# bqZUM_PowerManager.net
KiCad netlist of a schematic drawn in Altium Designer
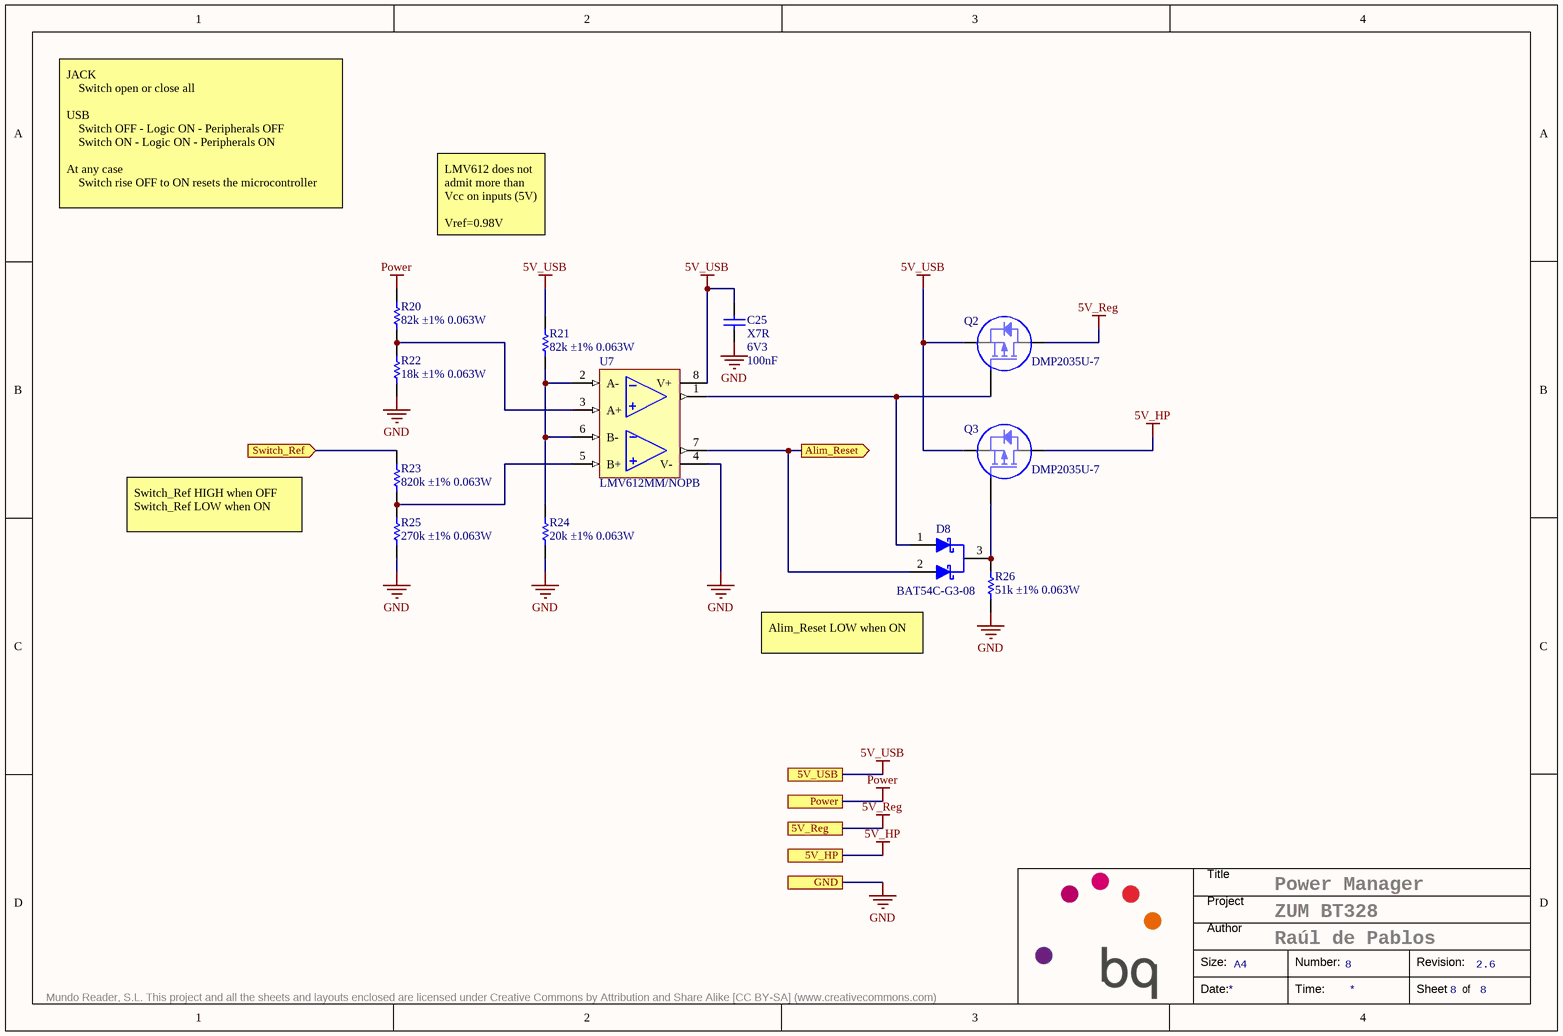
[diagram p0: bqZUM_PowerManager.SchDoc]

(export (version "E")
  (design (tool "Eeschema 10.0.6"))
  (components
    (comp (ref "C25")
      (value "Capacitor")
      (footprint "C0402")
      (fields
        (field (name "DIELECTRIC") "X7R")
        (field (name "VOLTAGE") "6V3")
        (field (name "CAPACITANCE") "100nF")
        (field (name "PART NUMBER") "C0402_100nF_6V3_±10%")
        (field (name "TOLERANCE") "±10%")
        (field (name "MANUFACTURER") "Kemet")
      )
      (libsource (lib "Pasives_Capacitor_SMD") (part "Capacitor"))
    )
    (comp (ref "D8")
      (value "BAT54C-G3-08")
      (footprint "SOT23-3")
      (description "Dual Schottky Diode Common Cathode")
      (fields (field (name "PART NUMBER") "BAT54C") (field (name "MANUFACTURER") "Vishay"))
      (libsource (lib "Semiconductors_Diodes") (part "Dual_Diode_Schottky_BAT54C"))
    )
    (comp (ref "Q2")
      (value "DMP2035U-7")
      (footprint "SOT23-3")
      (description "Mosfet Channel P Enhancement Mode")
      (fields (field (name "PART NUMBER") "DMP2035U") (field (name "MANUFACTURER") "Diodes Incorporated"))
      (libsource (lib "Semiconductors_Transistors") (part "Mosfet_P"))
    )
    (comp (ref "Q3")
      (value "DMP2035U-7")
      (footprint "SOT23-3")
      (description "Mosfet Channel P Enhancement Mode")
      (fields (field (name "PART NUMBER") "DMP2035U") (field (name "MANUFACTURER") "Diodes Incorporated"))
      (libsource (lib "Semiconductors_Transistors") (part "Mosfet_P"))
    )
    (comp (ref "R20")
      (value "82k ±1% 0.063W")
      (footprint "R0402")
      (description "Resistor")
      (fields (field (name "TOLERANCE") "±1%") (field (name "POWER") "0.063W"))
      (libsource (lib "Pasives_Resistor_SMD") (part "Resistor"))
    )
    (comp (ref "R21")
      (value "82k ±1% 0.063W")
      (footprint "R0402")
      (description "Resistor")
      (fields (field (name "TOLERANCE") "±1%") (field (name "POWER") "0.063W"))
      (libsource (lib "Pasives_Resistor_SMD") (part "Resistor"))
    )
    (comp (ref "R22")
      (value "18k ±1% 0.063W")
      (footprint "R0402")
      (description "Resistor")
      (fields (field (name "TOLERANCE") "±1%") (field (name "POWER") "0.063W"))
      (libsource (lib "Pasives_Resistor_SMD") (part "Resistor"))
    )
    (comp (ref "R23")
      (value "820k ±1% 0.063W")
      (footprint "R0402")
      (description "Resistor")
      (fields (field (name "TOLERANCE") "±1%") (field (name "POWER") "0.063W"))
      (libsource (lib "Pasives_Resistor_SMD") (part "Resistor"))
    )
    (comp (ref "R24")
      (value "20k ±1% 0.063W")
      (footprint "R0402")
      (description "Resistor")
      (fields (field (name "TOLERANCE") "±1%") (field (name "POWER") "0.063W"))
      (libsource (lib "Pasives_Resistor_SMD") (part "Resistor"))
    )
    (comp (ref "R25")
      (value "270k ±1% 0.063W")
      (footprint "R0402")
      (description "Resistor")
      (fields (field (name "TOLERANCE") "±1%") (field (name "POWER") "0.063W"))
      (libsource (lib "Pasives_Resistor_SMD") (part "Resistor"))
    )
    (comp (ref "R26")
      (value "51k ±1% 0.063W")
      (footprint "R0402")
      (description "Resistor")
      (fields (field (name "TOLERANCE") "±1%") (field (name "POWER") "0.063W"))
      (libsource (lib "Pasives_Resistor_SMD") (part "Resistor"))
    )
    (comp (ref "U7")
      (value "LMV612MM/NOPB")
      (footprint "VSSOP8")
      (description "Dual Operational Amplifier")
      (fields (field (name "PART NUMBER") "LMV612") (field (name "MANUFACTURER") "Texas Instruments"))
      (libsource (lib "Semiconductors_OA") (part "LMV612"))
    )
  )
  (nets
    (net (code "1") (name "/Alim_Reset") (class "Default")
      (node (ref "D8") (pin "2") (pinfunction "A2_2") (pintype "passive"))
      (node (ref "U7") (pin "7") (pinfunction "Out2_7") (pintype "output"))
    )
    (net (code "2") (name "/Switch_Ref") (class "Default")
      (node (ref "R23") (pin "2") (pinfunction "2_2") (pintype "passive"))
    )
    (net (code "3") (name "5V_HP") (class "Default")
      (node (ref "Q3") (pin "3") (pinfunction "D_3") (pintype "passive"))
    )
    (net (code "4") (name "5V_Reg") (class "Default")
      (node (ref "Q2") (pin "3") (pinfunction "D_3") (pintype "passive"))
    )
    (net (code "5") (name "5V_USB") (class "Default")
      (node (ref "C25") (pin "1") (pinfunction "1_1") (pintype "passive"))
      (node (ref "Q2") (pin "2") (pinfunction "S_2") (pintype "passive"))
      (node (ref "Q3") (pin "2") (pinfunction "S_2") (pintype "passive"))
      (node (ref "R21") (pin "2") (pinfunction "2_2") (pintype "passive"))
      (node (ref "U7") (pin "8") (pinfunction "V+_8") (pintype "power_in"))
    )
    (net (code "6") (name "GND") (class "Default")
      (node (ref "C25") (pin "2") (pinfunction "2_2") (pintype "passive"))
      (node (ref "R22") (pin "1") (pinfunction "1_1") (pintype "passive"))
      (node (ref "R24") (pin "1") (pinfunction "1_1") (pintype "passive"))
      (node (ref "R25") (pin "1") (pinfunction "1_1") (pintype "passive"))
      (node (ref "R26") (pin "1") (pinfunction "1_1") (pintype "passive"))
      (node (ref "U7") (pin "4") (pinfunction "V-_4") (pintype "power_in"))
    )
    (net (code "7") (name "Net-(D8-A1)") (class "Default")
      (node (ref "D8") (pin "1") (pinfunction "A1_1") (pintype "passive"))
      (node (ref "Q2") (pin "1") (pinfunction "G_1") (pintype "passive"))
      (node (ref "U7") (pin "1") (pinfunction "Out_1") (pintype "output"))
    )
    (net (code "8") (name "Net-(D8-K)") (class "Default")
      (node (ref "D8") (pin "3") (pinfunction "K_3") (pintype "passive"))
      (node (ref "Q3") (pin "1") (pinfunction "G_1") (pintype "passive"))
      (node (ref "R26") (pin "2") (pinfunction "2_2") (pintype "passive"))
    )
    (net (code "9") (name "Net-(U7-A+)") (class "Default")
      (node (ref "R20") (pin "1") (pinfunction "1_1") (pintype "passive"))
      (node (ref "R22") (pin "2") (pinfunction "2_2") (pintype "passive"))
      (node (ref "U7") (pin "3") (pinfunction "A+_3") (pintype "input"))
    )
    (net (code "10") (name "Net-(U7-A-)") (class "Default")
      (node (ref "R21") (pin "1") (pinfunction "1_1") (pintype "passive"))
      (node (ref "R24") (pin "2") (pinfunction "2_2") (pintype "passive"))
      (node (ref "U7") (pin "2") (pinfunction "A-_2") (pintype "input"))
      (node (ref "U7") (pin "6") (pinfunction "B-_6") (pintype "input"))
    )
    (net (code "11") (name "Net-(U7-B+)") (class "Default")
      (node (ref "R23") (pin "1") (pinfunction "1_1") (pintype "passive"))
      (node (ref "R25") (pin "2") (pinfunction "2_2") (pintype "passive"))
      (node (ref "U7") (pin "5") (pinfunction "B+_5") (pintype "input"))
    )
    (net (code "12") (name "Power") (class "Default")
      (node (ref "R20") (pin "2") (pinfunction "2_2") (pintype "passive"))
    )
  )
)
